# Pack_Interface.net
KiCad netlist of a schematic drawn in Altium Designer
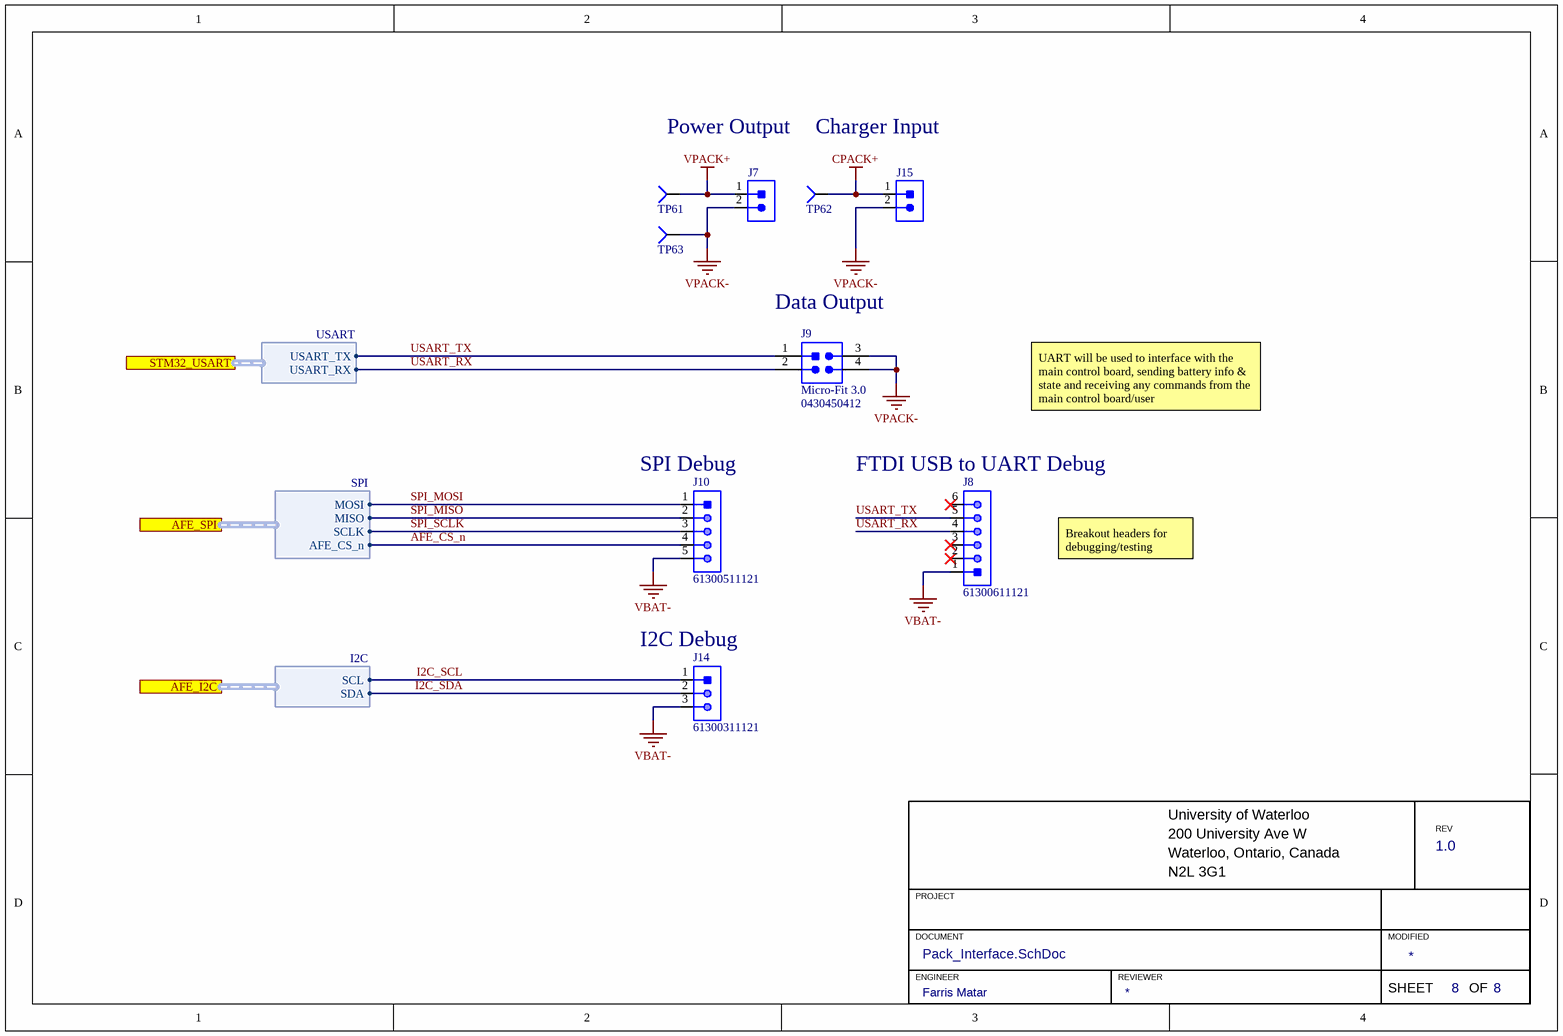
[diagram p0: Pack_Interface.SchDoc]

(export (version "E")
  (design (tool "Eeschema 10.0.6"))
  (components
    (comp (ref "J7")
      (value "CON_2POS_XT90")
      (footprint "XT90")
      (description "HIGH QUALITY GOLD PLATED XT90 MA")
      (libsource (lib "Personal_Schematic_Library_2022") (part "CON_2POS_XT90"))
    )
    (comp (ref "J8")
      (value "HEADER 6x1")
      (footprint "HDR1X6")
      (description "CONN HEADER VERT 6POS 2.54MM")
      (fields (field (name "MANUFACTURER PART NUMBER 1") "61300611121"))
      (libsource (lib "Personal_Schematic_Library_2022") (part "HEADER 6x1"))
    )
    (comp (ref "J9")
      (value "0430450412")
      (footprint "MOLEX-0430450412")
      (description "CONN HEADER VERT 4POS 3MM")
      (fields
        (field (name "FAMILY") "Micro-Fit 3.0")
        (field (name "MANUFACTURER PART NUMBER 1") "0430450412")
      )
      (libsource (lib "Personal_Schematic_Library_2022") (part "CON_MOLEX-HDR_2x2_TH"))
    )
    (comp (ref "J10")
      (value "HEADER 5x1")
      (footprint "HDR1X5")
      (description "CONN HEADER VERT 5POS 2.54MM")
      (fields (field (name "MANUFACTURER PART NUMBER 1") "61300511121"))
      (libsource (lib "Personal_Schematic_Library_2022") (part "HEADER 5x1"))
    )
    (comp (ref "J14")
      (value "HEADER 3x1")
      (footprint "HDR1X3")
      (description "CONN HEADER VERT 3POS 2.54MM")
      (fields (field (name "MANUFACTURER PART NUMBER 1") "61300311121"))
      (libsource (lib "Personal_Schematic_Library_2022") (part "HEADER 3x1"))
    )
    (comp (ref "J15")
      (value "CON_2POS_XT90")
      (footprint "XT90")
      (description "HIGH QUALITY GOLD PLATED XT90 MA")
      (libsource (lib "Personal_Schematic_Library_2022") (part "CON_2POS_XT90"))
    )
    (comp (ref "TP61")
      (value "TESTPOINT_SMD_LOOP")
      (footprint "S1751-46R")
      (description "TESTPOINT SMD LOOP")
      (libsource (lib "UWRT_Schematic_Library_2020") (part "TESTPOINT_SMD_LOOP"))
    )
    (comp (ref "TP62")
      (value "TESTPOINT_SMD_LOOP")
      (footprint "S1751-46R")
      (description "TESTPOINT SMD LOOP")
      (libsource (lib "UWRT_Schematic_Library_2020") (part "TESTPOINT_SMD_LOOP"))
    )
    (comp (ref "TP63")
      (value "TESTPOINT_SMD_LOOP")
      (footprint "S1751-46R")
      (description "TESTPOINT SMD LOOP")
      (libsource (lib "UWRT_Schematic_Library_2020") (part "TESTPOINT_SMD_LOOP"))
    )
  )
  (nets
    (net (code "4") (name "/AFE_CS_n") (class "Default")
      (node (ref "J10") (pin "4") (pinfunction "4_4") (pintype "passive"))
    )
    (net (code "5") (name "/I2C_SCL") (class "Default")
      (node (ref "J14") (pin "1") (pinfunction "1_1") (pintype "passive"))
    )
    (net (code "6") (name "/I2C_SDA") (class "Default")
      (node (ref "J14") (pin "2") (pinfunction "2_2") (pintype "passive"))
    )
    (net (code "7") (name "/SPI_MISO") (class "Default")
      (node (ref "J10") (pin "2") (pinfunction "2_2") (pintype "passive"))
    )
    (net (code "8") (name "/SPI_MOSI") (class "Default")
      (node (ref "J10") (pin "1") (pinfunction "1_1") (pintype "passive"))
    )
    (net (code "9") (name "/SPI_SCLK") (class "Default")
      (node (ref "J10") (pin "3") (pinfunction "3_3") (pintype "passive"))
    )
    (net (code "10") (name "/USART_RX") (class "Default")
      (node (ref "J8") (pin "4") (pinfunction "4_4") (pintype "passive"))
      (node (ref "J9") (pin "2") (pinfunction "2_2") (pintype "passive"))
    )
    (net (code "11") (name "/USART_TX") (class "Default")
      (node (ref "J8") (pin "5") (pinfunction "5_5") (pintype "passive"))
      (node (ref "J9") (pin "1") (pinfunction "1_1") (pintype "passive"))
    )
    (net (code "15") (name "CPACK+") (class "Default")
      (node (ref "J15") (pin "1") (pinfunction "1_1") (pintype "passive"))
      (node (ref "TP62") (pin "1") (pinfunction "=value_1") (pintype "passive"))
    )
    (net (code "16") (name "VBAT-") (class "Default")
      (node (ref "J10") (pin "5") (pinfunction "5_5") (pintype "passive"))
      (node (ref "J14") (pin "3") (pinfunction "3_3") (pintype "passive"))
      (node (ref "J8") (pin "1") (pinfunction "1_1") (pintype "passive"))
    )
    (net (code "17") (name "VPACK+") (class "Default")
      (node (ref "J7") (pin "1") (pinfunction "1_1") (pintype "passive"))
      (node (ref "TP61") (pin "1") (pinfunction "=value_1") (pintype "passive"))
    )
    (net (code "18") (name "VPACK-") (class "Default")
      (node (ref "J15") (pin "2") (pinfunction "2_2") (pintype "passive"))
      (node (ref "J7") (pin "2") (pinfunction "2_2") (pintype "passive"))
      (node (ref "J9") (pin "3") (pinfunction "3_3") (pintype "passive"))
      (node (ref "J9") (pin "4") (pinfunction "4_4") (pintype "passive"))
      (node (ref "TP63") (pin "1") (pinfunction "=value_1") (pintype "passive"))
    )
    (net (code "19") (name "unconnected-(J8-Pad2)") (class "Default")
      (node (ref "J8") (pin "2") (pinfunction "2_2") (pintype "passive+no_connect"))
    )
    (net (code "20") (name "unconnected-(J8-Pad3)") (class "Default")
      (node (ref "J8") (pin "3") (pinfunction "3_3") (pintype "passive+no_connect"))
    )
    (net (code "21") (name "unconnected-(J8-Pad6)") (class "Default")
      (node (ref "J8") (pin "6") (pinfunction "6_6") (pintype "passive+no_connect"))
    )
  )
)
